# Oscillatore_Variabile_Del_Volume.net
KiCad netlist of a schematic drawn in EAGLE
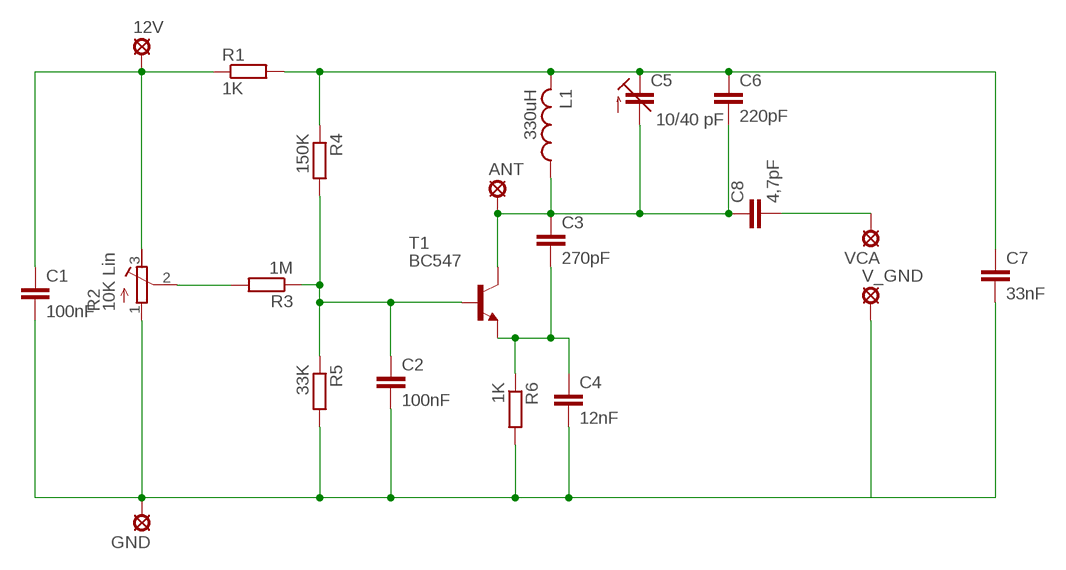
[diagram p0: schematic, sheet 1]

(export (version "E")
  (design (tool "Eeschema 10.0.6"))
  (components
    (comp (ref "12V")
      (value "LSP13")
      (footprint "eagle-import:LSP13")
      (libsource (lib "eagle-import") (part "LSP13"))
    )
    (comp (ref "ANT")
      (value "LSP10")
      (footprint "eagle-import:LSP10")
      (libsource (lib "eagle-import") (part "LSP10"))
    )
    (comp (ref "C1")
      (value "100nF")
      (footprint "eagle-import:C7.5B3")
      (libsource (lib "eagle-import") (part "C7.5/3"))
    )
    (comp (ref "C2")
      (value "100nF")
      (footprint "eagle-import:C7.5B3")
      (libsource (lib "eagle-import") (part "C7.5/3"))
    )
    (comp (ref "C3")
      (value "270pF")
      (footprint "eagle-import:C7.5B3")
      (libsource (lib "eagle-import") (part "C7.5/3"))
    )
    (comp (ref "C4")
      (value "12nF")
      (footprint "eagle-import:C7.5B3")
      (libsource (lib "eagle-import") (part "C7.5/3"))
    )
    (comp (ref "C5")
      (value "10/40 pF")
      (footprint "eagle-import:3008")
      (libsource (lib "eagle-import") (part "C-TRIMM3008"))
    )
    (comp (ref "C6")
      (value "220pF")
      (footprint "eagle-import:C7.5B3")
      (libsource (lib "eagle-import") (part "C7.5/3"))
    )
    (comp (ref "C7")
      (value "33nF")
      (footprint "eagle-import:C7.5B3")
      (libsource (lib "eagle-import") (part "C7.5/3"))
    )
    (comp (ref "C8")
      (value "4,7pF")
      (footprint "eagle-import:C2.5-5")
      (libsource (lib "eagle-import") (part "C2.5/5"))
    )
    (comp (ref "GND")
      (value "LSP13")
      (footprint "eagle-import:LSP13")
      (libsource (lib "eagle-import") (part "LSP13"))
    )
    (comp (ref "L1")
      (value "330uH")
      (footprint "eagle-import:0204_7")
      (libsource (lib "eagle-import") (part "L-US0204/7"))
    )
    (comp (ref "R1")
      (value "1K")
      (footprint "eagle-import:0207_10")
      (libsource (lib "eagle-import") (part "R-EU_0207/10"))
    )
    (comp (ref "R2")
      (value "10K Lin")
      (footprint "eagle-import:RTRIM3339P")
      (libsource (lib "eagle-import") (part "R-TRIMM3339P"))
    )
    (comp (ref "R3")
      (value "1M")
      (footprint "eagle-import:0207_10")
      (libsource (lib "eagle-import") (part "R-EU_0207/10"))
    )
    (comp (ref "R4")
      (value "150K")
      (footprint "eagle-import:0207_10")
      (libsource (lib "eagle-import") (part "R-EU_0207/10"))
    )
    (comp (ref "R5")
      (value "33K")
      (footprint "eagle-import:0207_10")
      (libsource (lib "eagle-import") (part "R-EU_0207/10"))
    )
    (comp (ref "R6")
      (value "1K")
      (footprint "eagle-import:0207_10")
      (libsource (lib "eagle-import") (part "R-EU_0207/10"))
    )
    (comp (ref "T1")
      (value "BC547")
      (footprint "eagle-import:TO92")
      (libsource (lib "eagle-import") (part "BC547"))
    )
    (comp (ref "VCA")
      (value "LSP13")
      (footprint "eagle-import:LSP13")
      (libsource (lib "eagle-import") (part "LSP13"))
    )
    (comp (ref "V_GND")
      (value "LSP13")
      (footprint "eagle-import:LSP13")
      (libsource (lib "eagle-import") (part "LSP13"))
    )
  )
  (nets
    (net (code "1") (name "Net-(C5-A)") (class "Default")
      (node (ref "ANT") (pin "MP") (pinfunction "MP_MP") (pintype "passive"))
      (node (ref "C3") (pin "1") (pinfunction "1_1") (pintype "passive"))
      (node (ref "C5") (pin "-") (pinfunction "A_-") (pintype "passive"))
      (node (ref "C6") (pin "2") (pinfunction "2_2") (pintype "passive"))
      (node (ref "C8") (pin "1") (pinfunction "1_1") (pintype "passive"))
      (node (ref "L1") (pin "1") (pinfunction "1_1") (pintype "passive"))
      (node (ref "T1") (pin "3") (pinfunction "C_3") (pintype "passive"))
    )
    (net (code "2") (name "Net-(C5-E)") (class "Default")
      (node (ref "C5") (pin "+") (pinfunction "E_+") (pintype "passive"))
      (node (ref "C6") (pin "1") (pinfunction "1_1") (pintype "passive"))
      (node (ref "C7") (pin "1") (pinfunction "1_1") (pintype "passive"))
      (node (ref "L1") (pin "2") (pinfunction "2_2") (pintype "passive"))
      (node (ref "R1") (pin "2") (pinfunction "2_2") (pintype "passive"))
      (node (ref "R4") (pin "1") (pinfunction "1_1") (pintype "passive"))
    )
    (net (code "3") (name "Net-(C8-Pad2)") (class "Default")
      (node (ref "C8") (pin "2") (pinfunction "2_2") (pintype "passive"))
      (node (ref "VCA") (pin "MP") (pinfunction "MP_MP") (pintype "passive"))
    )
    (net (code "4") (name "Net-(R2-A)") (class "Default")
      (node (ref "C1") (pin "2") (pinfunction "2_2") (pintype "passive"))
      (node (ref "C2") (pin "2") (pinfunction "2_2") (pintype "passive"))
      (node (ref "C4") (pin "2") (pinfunction "2_2") (pintype "passive"))
      (node (ref "C7") (pin "2") (pinfunction "2_2") (pintype "passive"))
      (node (ref "GND") (pin "MP") (pinfunction "MP_MP") (pintype "passive"))
      (node (ref "R2") (pin "1") (pinfunction "A_1") (pintype "passive"))
      (node (ref "R5") (pin "2") (pinfunction "2_2") (pintype "passive"))
      (node (ref "R6") (pin "2") (pinfunction "2_2") (pintype "passive"))
      (node (ref "V_GND") (pin "MP") (pinfunction "MP_MP") (pintype "passive"))
    )
    (net (code "5") (name "Net-(R2-E)") (class "Default")
      (node (ref "12V") (pin "MP") (pinfunction "MP_MP") (pintype "passive"))
      (node (ref "C1") (pin "1") (pinfunction "1_1") (pintype "passive"))
      (node (ref "R1") (pin "1") (pinfunction "1_1") (pintype "passive"))
      (node (ref "R2") (pin "3") (pinfunction "E_3") (pintype "passive"))
    )
    (net (code "6") (name "Net-(R2-S)") (class "Default")
      (node (ref "R2") (pin "2") (pinfunction "S_2") (pintype "passive"))
      (node (ref "R3") (pin "2") (pinfunction "2_2") (pintype "passive"))
    )
    (net (code "7") (name "Net-(T1-B)") (class "Default")
      (node (ref "C2") (pin "1") (pinfunction "1_1") (pintype "passive"))
      (node (ref "R3") (pin "1") (pinfunction "1_1") (pintype "passive"))
      (node (ref "R4") (pin "2") (pinfunction "2_2") (pintype "passive"))
      (node (ref "R5") (pin "1") (pinfunction "1_1") (pintype "passive"))
      (node (ref "T1") (pin "2") (pinfunction "B_2") (pintype "passive"))
    )
    (net (code "8") (name "Net-(T1-E)") (class "Default")
      (node (ref "C3") (pin "2") (pinfunction "2_2") (pintype "passive"))
      (node (ref "C4") (pin "1") (pinfunction "1_1") (pintype "passive"))
      (node (ref "R6") (pin "1") (pinfunction "1_1") (pintype "passive"))
      (node (ref "T1") (pin "1") (pinfunction "E_1") (pintype "passive"))
    )
  )
)
